# Page_1.net
KiCad netlist of a schematic drawn in Altium Designer
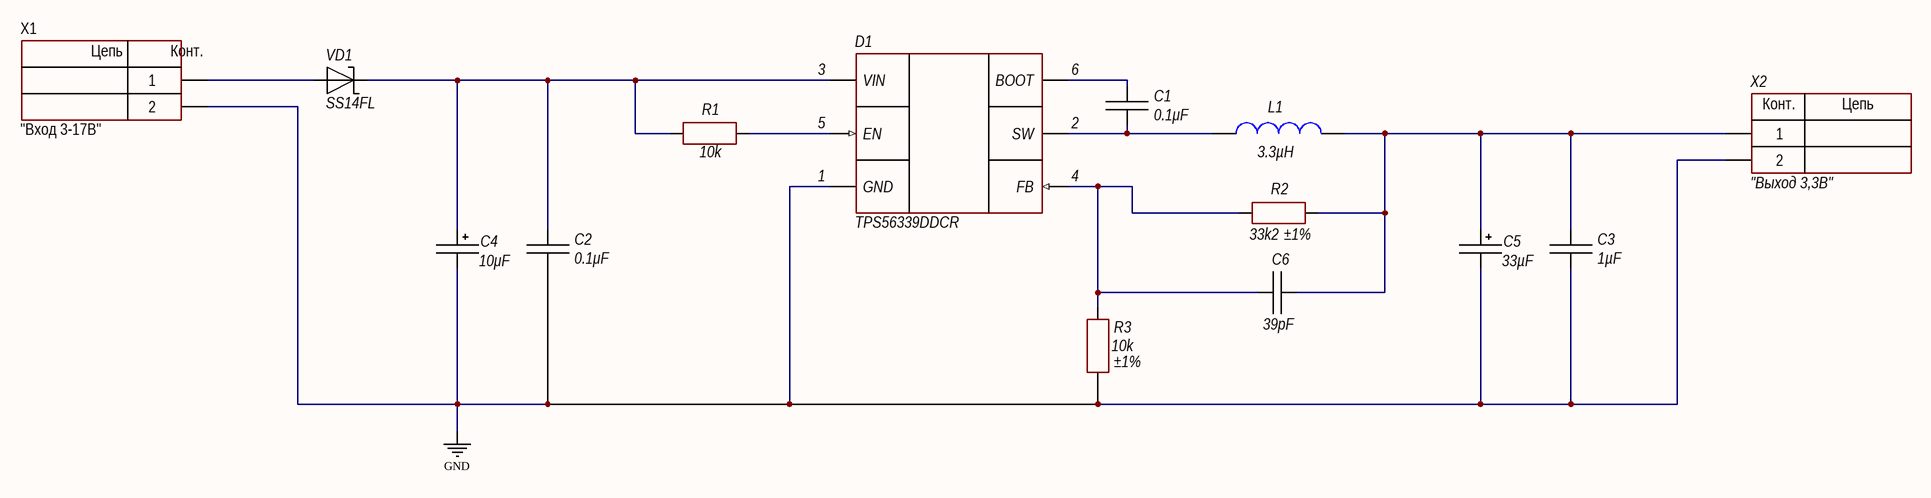
[diagram p0: Page#1.SchDoc]

(export (version "E")
  (design (tool "Eeschema 10.0.6"))
  (components
    (comp (ref "C1")
      (value "0.1μF")
      (footprint "StandardCase:CAP: 0603")
      (fields
        (field (name "MANUFACTURER") "Murata Electronics")
        (field (name "PARTNUMBER") "GCJ188R71E104KA12D")
        (field (name "VALUEMANUFACTURERPARTNUMBER") "Ceramic capacitor, 0.1μF, X7R, ±10%, 16V, 0603, -55...+125°C")
      )
      (libsource (lib "Capacitor") (part "Ceramic_0603"))
    )
    (comp (ref "C2")
      (value "0.1μF")
      (footprint "StandardCase:CAP: 0603")
      (fields
        (field (name "MANUFACTURER") "Murata Electronics")
        (field (name "PARTNUMBER") "GCJ188R71E104KA12D")
        (field (name "VALUEMANUFACTURERPARTNUMBER") "Ceramic capacitor, 0.1μF, X7R, ±10%, 16V, 0603, -55...+125°C")
      )
      (libsource (lib "Capacitor") (part "Ceramic_0603"))
    )
    (comp (ref "C3")
      (value "1µF")
      (footprint "StandardCase:CAP: 0603")
      (fields
        (field (name "MANUFACTURER") "Murata Electronics")
        (field (name "PARTNUMBER") "GRM188R61C105KA12D")
        (field (name "VALUEMANUFACTURERPARTNUMBER") "Ceramic capacitor, 1µF, X5R, ±10%, 16V, 0603, -55°C ~ 85°C")
      )
      (libsource (lib "Capacitor") (part "Ceramic_0603"))
    )
    (comp (ref "C4")
      (value "10μF")
      (footprint "StandardCase:CAP: TANTAL-A")
      (fields
        (field (name "MANUFACTURER") "AVX Corporation")
        (field (name "PARTNUMBER") "TCJA106M020R0150")
        (field (name "VALUEMANUFACTURERPARTNUMBER") "Tantalum capacitor, 10μF, 20V, ±10%, 2Ohm, case A (3216), -55...+125°C")
      )
      (libsource (lib "Capacitor") (part "Tantal_A"))
    )
    (comp (ref "C5")
      (value "33µF")
      (footprint "StandardCase:CAP: TANTAL-A")
      (fields
        (field (name "MANUFACTURER") "Vishay Sprague")
        (field (name "PARTNUMBER") "T55A336M6R3C0200")
        (field (name "VALUEMANUFACTURERPARTNUMBER") "Tantalum capacitor, 33µF, 6.3V, ±20%, 2Ohm, case A (3216), -55...+125°C")
      )
      (libsource (lib "Capacitor") (part "Tantal_A"))
    )
    (comp (ref "C6")
      (value "39pF")
      (footprint "StandardCase:CAP: 0603")
      (fields
        (field (name "MANUFACTURER") "Murata Electronics")
        (field (name "PARTNUMBER") "GRM1885C1H390JA01D")
        (field (name "VALUEMANUFACTURERPARTNUMBER") "Ceramic capacitor, 39pF, C0G, NP0, ±5%, 50V, 0603, -55°C ~ 125°C")
      )
      (libsource (lib "Capacitor") (part "Ceramic_0603"))
    )
    (comp (ref "D1")
      (value "~")
      (footprint "StandardCase:SOT23-6")
      (description "Sync buck converter")
      (fields
        (field (name "MANUFACTURER") "Texas Instruments")
        (field (name "VALUEMANUFACTURERPARTNUMBER") "DC/DC sync buck converter, input 4.5...24V, 500 kHz, output 0.8...16V, 3A, -40...+125°C, TSOT-23-6")
        (field (name "PARTNUMBER") "TPS56339DDCR")
      )
      (libsource (lib "IC. Power supply") (part "TPS56339DDCR"))
    )
    (comp (ref "L1")
      (value "3.3µH")
      (footprint "CustomCase:IND: SDR0403")
      (fields
        (field (name "MANUFACTURER") "Bourns")
        (field (name "PARTNUMBER") "SDR0403-3R3ML")
        (field (name "VALUEMANUFACTURERPARTNUMBER") "Wirewound, 3.3µH, ±20%, SDR0403, 3A, -40...+125°C")
      )
      (libsource (lib "Inductor") (part "Inductor_SDR0403"))
    )
    (comp (ref "R1")
      (value "10k")
      (footprint "StandardCase:RES: 0603")
      (fields
        (field (name "MANUFACTURER") "Yageo")
        (field (name "PARTNUMBER") "RC0603FR-0710KL")
        (field (name "VALUEMANUFACTURERPARTNUMBER") "Resistor film, 10k, ±1%, 0603, 0.1W, -55°C ~ 155°C")
      )
      (libsource (lib "") (part "Resistor_0603_2"))
    )
    (comp (ref "R2")
      (value "33k2")
      (footprint "StandardCase:RES: 0603")
      (fields
        (field (name "MANUFACTURER") "Yageo")
        (field (name "PARTNUMBER") "RC0603FR-0733K2L")
        (field (name "VALUEMANUFACTURERPARTNUMBER") "Thick Film, 33k2, ±1%, 0603, 0.1W, -55°C ~ 155°C")
        (field (name "TOLERANCE") "±1%")
      )
      (libsource (lib "Resistor") (part "Resistor_0603"))
    )
    (comp (ref "R3")
      (value "10k")
      (footprint "StandardCase:RES: 0603")
      (fields
        (field (name "MANUFACTURER") "Yageo")
        (field (name "PARTNUMBER") "RC0603FR-0710KL")
        (field (name "VALUEMANUFACTURERPARTNUMBER") "Resistor film, 10k, ±1%, 0603, 0.1W, -55°C ~ 155°C")
        (field (name "TOLERANCE") "±1%")
      )
      (libsource (lib "") (part "Resistor_0603_1"))
    )
    (comp (ref "VD1")
      (value "SS14FL")
      (footprint "StandardCase:DIODE: SOD123F")
      (fields
        (field (name "MANUFACTURER") "ON Semiconductor")
        (field (name "VALUEMANUFACTURERPARTNUMBER") "Schottky diode, 40V, 1A, 1V, 15pF, SOD-123F, -55°C ~ 125°C")
        (field (name "VOLTAGE") "40V")
        (field (name "PARTNUMBER") "SS14FL")
      )
      (libsource (lib "Diode") (part "Schottky_single"))
    )
    (comp (ref "X1")
      (value "~")
      (footprint "CustomCase:CON: 0533750210")
      (fields
        (field (name "MANUFACTURER") "Molex")
        (field (name "VALUEMANUFACTURERPARTNUMBER") "Connector, 2pin, 2.50mm, 250V, 3A")
        (field (name "PARTNUMBER") "0533750210")
        (field (name "COMMENTTEXT") "\"Вход 3-17В\"")
      )
      (libsource (lib "Connector") (part "CWF-2R"))
    )
    (comp (ref "X2")
      (value "\"Выход 3,3В\"")
      (footprint "CustomCase:CON: 0533750210")
      (fields
        (field (name "MANUFACTURER") "Molex")
        (field (name "VALUEMANUFACTURERPARTNUMBER") "Connector, 2pin, 9.53mm, 300VAC, 25A")
        (field (name "PARTNUMBER") "0533750210")
      )
      (libsource (lib "Connector") (part "Connector_6PCV-02"))
    )
  )
  (nets
    (net (code "1") (name "GND") (class "Default")
      (node (ref "C2") (pin "1") (pinfunction "1_1") (pintype "power_in"))
      (node (ref "C3") (pin "1") (pinfunction "1_1") (pintype "power_in"))
      (node (ref "C4") (pin "2") (pinfunction "2_2") (pintype "power_in"))
      (node (ref "C5") (pin "2") (pinfunction "2_2") (pintype "power_in"))
      (node (ref "D1") (pin "1") (pinfunction "GND_1") (pintype "passive"))
      (node (ref "R3") (pin "1") (pinfunction "1_1") (pintype "passive"))
      (node (ref "X1") (pin "2") (pinfunction "2_2") (pintype "passive"))
      (node (ref "X2") (pin "2") (pinfunction "2_2") (pintype "passive"))
    )
    (net (code "2") (name "Net-(C3-Pad2)") (class "Default")
      (node (ref "C3") (pin "2") (pinfunction "2_2") (pintype "power_in"))
      (node (ref "C5") (pin "1") (pinfunction "1_1") (pintype "power_in"))
      (node (ref "C6") (pin "1") (pinfunction "1_1") (pintype "power_in"))
      (node (ref "L1") (pin "1") (pinfunction "1_1") (pintype "passive"))
      (node (ref "R2") (pin "2") (pinfunction "2_2") (pintype "passive"))
      (node (ref "X2") (pin "1") (pinfunction "1_1") (pintype "passive"))
    )
    (net (code "3") (name "Net-(D1-BOOT)") (class "Default")
      (node (ref "C1") (pin "2") (pinfunction "2_2") (pintype "power_in"))
      (node (ref "D1") (pin "6") (pinfunction "BOOT_6") (pintype "passive"))
    )
    (net (code "4") (name "Net-(D1-EN)") (class "Default")
      (node (ref "D1") (pin "5") (pinfunction "EN_5") (pintype "input"))
      (node (ref "R1") (pin "1") (pinfunction "1_1") (pintype "passive"))
    )
    (net (code "5") (name "Net-(D1-FB)") (class "Default")
      (node (ref "C6") (pin "2") (pinfunction "2_2") (pintype "power_in"))
      (node (ref "D1") (pin "4") (pinfunction "FB_4") (pintype "input"))
      (node (ref "R2") (pin "1") (pinfunction "1_1") (pintype "passive"))
      (node (ref "R3") (pin "2") (pinfunction "2_2") (pintype "passive"))
    )
    (net (code "6") (name "Net-(D1-SW)") (class "Default")
      (node (ref "C1") (pin "1") (pinfunction "1_1") (pintype "power_in"))
      (node (ref "D1") (pin "2") (pinfunction "SW_2") (pintype "passive"))
      (node (ref "L1") (pin "2") (pinfunction "2_2") (pintype "passive"))
    )
    (net (code "7") (name "Net-(D1-VIN)") (class "Default")
      (node (ref "C2") (pin "2") (pinfunction "2_2") (pintype "power_in"))
      (node (ref "C4") (pin "1") (pinfunction "1_1") (pintype "power_in"))
      (node (ref "D1") (pin "3") (pinfunction "VIN_3") (pintype "passive"))
      (node (ref "R1") (pin "2") (pinfunction "2_2") (pintype "passive"))
      (node (ref "VD1") (pin "2") (pinfunction "2_2") (pintype "passive"))
    )
    (net (code "8") (name "Net-(VD1-Pad1)") (class "Default")
      (node (ref "VD1") (pin "1") (pinfunction "1_1") (pintype "passive"))
      (node (ref "X1") (pin "1") (pinfunction "1_1") (pintype "passive"))
    )
  )
)
